# femtoUSB_r1_0_0_panelized.net
KiCad netlist of a schematic drawn in EAGLE
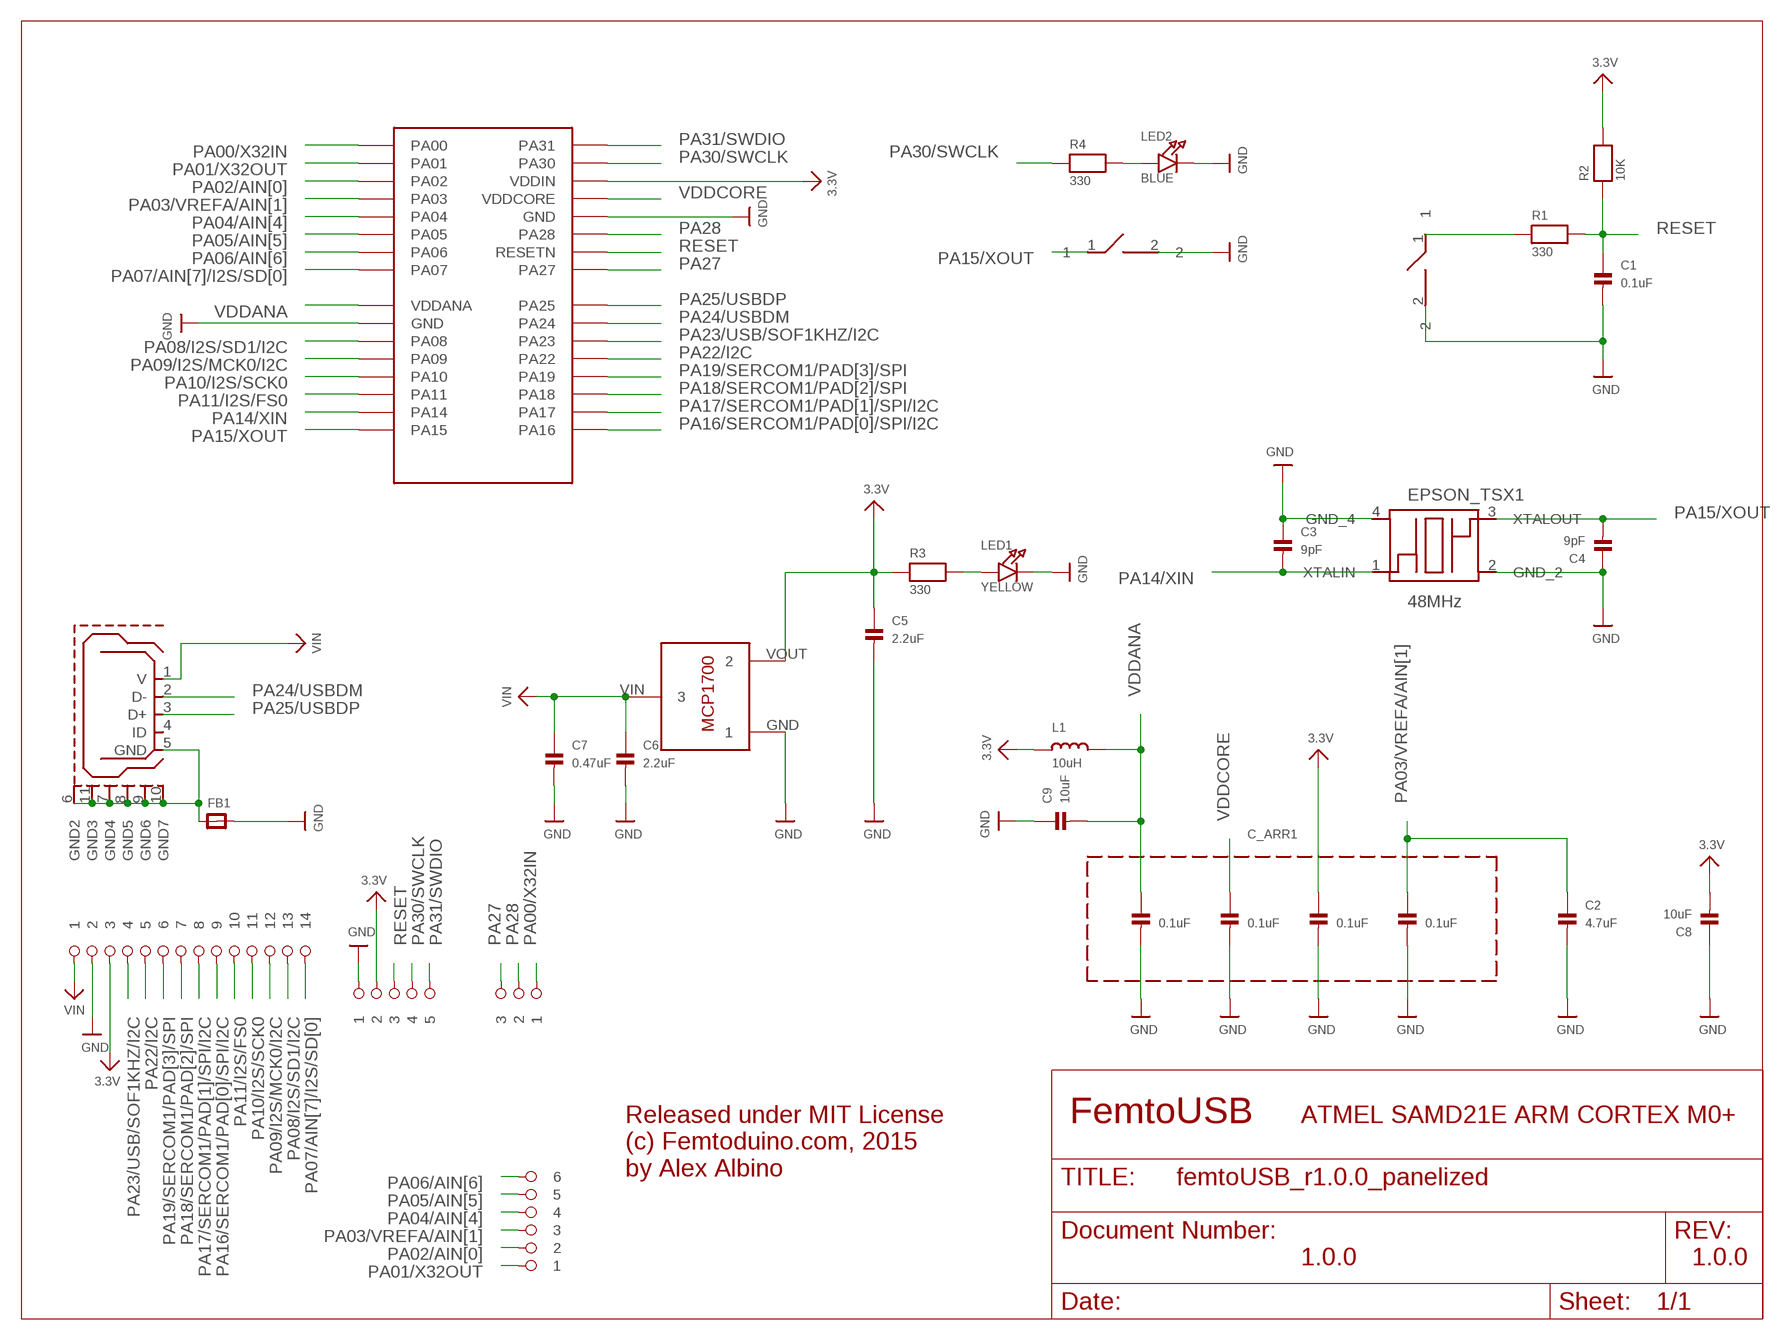
[diagram p0: schematic, sheet 1]

(export (version "E")
  (design (tool "Eeschema 10.0.6"))
  (components
    (comp (ref "BTN")
      (value "OMRON B3U-300P(M)")
      (footprint "eagle-import:SPST_SMD")
      (libsource (lib "eagle-import") (part "SPST_SMD"))
    )
    (comp (ref "C1")
      (value "0.1uF")
      (footprint "eagle-import:_0402MP")
      (libsource (lib "eagle-import") (part "CAP_CERAMIC_0402MP"))
    )
    (comp (ref "C2")
      (value "4.7uF")
      (footprint "eagle-import:_0402MP")
      (libsource (lib "eagle-import") (part "CAP_CERAMIC_0402MP"))
    )
    (comp (ref "C3")
      (value "9pF")
      (footprint "eagle-import:_0402MP")
      (libsource (lib "eagle-import") (part "CAP_CERAMIC_0402MP"))
    )
    (comp (ref "C4")
      (value "9pF")
      (footprint "eagle-import:_0402MP")
      (libsource (lib "eagle-import") (part "CAP_CERAMIC_0402MP"))
    )
    (comp (ref "C5")
      (value "2.2uF")
      (footprint "eagle-import:_0402MP")
      (libsource (lib "eagle-import") (part "CAP_CERAMIC_0402MP"))
    )
    (comp (ref "C6")
      (value "2.2uF")
      (footprint "eagle-import:_0402MP")
      (libsource (lib "eagle-import") (part "CAP_CERAMIC_0402MP"))
    )
    (comp (ref "C7")
      (value "0.47uF")
      (footprint "eagle-import:_0402MP")
      (libsource (lib "eagle-import") (part "CAP_CERAMIC_0402MP"))
    )
    (comp (ref "C8")
      (value "10uF")
      (footprint "eagle-import:_0402MP")
      (libsource (lib "eagle-import") (part "CAP_CERAMIC_0402MP"))
    )
    (comp (ref "C9")
      (value "10uF")
      (footprint "eagle-import:_0402MP")
      (libsource (lib "eagle-import") (part "CAP_CERAMIC_0402MP"))
    )
    (comp (ref "C_ARR1")
      (value "0.1uF")
      (footprint "eagle-import:CAPACITOR_ARRAY_1206_MONO_1X4")
      (libsource (lib "eagle-import") (part "KEMET_CERAMIC_CAPACITOR_ARRAY_1X4"))
    )
    (comp (ref "EPSON_TSX1")
      (value "48MHz")
      (footprint "eagle-import:TSX-3225")
      (fields (field (name "DIGIKEY_PART") "TSX-3225 32.0000MF15X-B-ND"))
      (libsource (lib "eagle-import") (part "TSX-3225"))
    )
    (comp (ref "FB1")
      (value "FERRITE_0603MP")
      (footprint "eagle-import:_0603MP")
      (libsource (lib "eagle-import") (part "FERRITE_0603MP"))
    )
    (comp (ref "IC1")
      (value "ATSAMD21E18A-MUT")
      (footprint "eagle-import:QFN32")
      (libsource (lib "eagle-import") (part "ATSAMD21E18A-MUT"))
    )
    (comp (ref "L1")
      (value "10uH")
      (footprint "eagle-import:_0603MP")
      (libsource (lib "eagle-import") (part "INDUCTOR_0603MP"))
    )
    (comp (ref "LDO_VREG")
      (value "MCP1700T-3302E/TT")
      (footprint "eagle-import:MCP1700T-3302E_TT")
      (libsource (lib "eagle-import") (part "MCP1700T-3302E/TT"))
    )
    (comp (ref "LED1")
      (value "YELLOW")
      (footprint "eagle-import:CHIPLED_0603_NOOUTLINE")
      (libsource (lib "eagle-import") (part "LED0603_NOOUTLINE"))
    )
    (comp (ref "LED2")
      (value "BLUE")
      (footprint "eagle-import:CHIPLED_0603_NOOUTLINE")
      (libsource (lib "eagle-import") (part "LED0603_NOOUTLINE"))
    )
    (comp (ref "MICRO_B_USB")
      (value "USB_MICROB")
      (footprint "eagle-import:USB_MICROB_PACKAGE")
      (libsource (lib "eagle-import") (part "USB_MICROB"))
    )
    (comp (ref "R1")
      (value "330")
      (footprint "eagle-import:_0402MP")
      (libsource (lib "eagle-import") (part "RESISTOR_0402MP"))
    )
    (comp (ref "R2")
      (value "10K")
      (footprint "eagle-import:_0402MP")
      (libsource (lib "eagle-import") (part "RESISTOR_0402MP"))
    )
    (comp (ref "R3")
      (value "330")
      (footprint "eagle-import:_0402MP")
      (libsource (lib "eagle-import") (part "RESISTOR_0402MP"))
    )
    (comp (ref "R4")
      (value "330")
      (footprint "eagle-import:_0402MP")
      (libsource (lib "eagle-import") (part "RESISTOR_0402MP"))
    )
    (comp (ref "U$6")
      (value "1X14_ROUND")
      (footprint "eagle-import:1X14_ROUND")
      (libsource (lib "eagle-import") (part "1X14_ROUND"))
    )
    (comp (ref "U$7")
      (value "1X3_ROUND")
      (footprint "eagle-import:1X3_ROUND")
      (libsource (lib "eagle-import") (part "1X3_ROUND"))
    )
    (comp (ref "U$9")
      (value "1X5_ROUND")
      (footprint "eagle-import:1X5_ROUND")
      (libsource (lib "eagle-import") (part "1X5_ROUND"))
    )
    (comp (ref "U$12")
      (value "1X6_ROUND")
      (footprint "eagle-import:1X6_ROUND")
      (libsource (lib "eagle-import") (part "1X6_ROUND"))
    )
    (comp (ref "U$38")
      (value "SPST_SMD")
      (footprint "eagle-import:SPST_SMD")
      (libsource (lib "eagle-import") (part "SPST_SMD"))
    )
  )
  (nets
    (net (code "1") (name "/PA00{slash}X32IN") (class "Default")
      (node (ref "IC1") (pin "1") (pinfunction "PA00_1") (pintype "bidirectional"))
      (node (ref "U$7") (pin "P$1") (pinfunction "1_P$1") (pintype "bidirectional"))
    )
    (net (code "2") (name "/PA01{slash}X32OUT") (class "Default")
      (node (ref "IC1") (pin "2") (pinfunction "PA01_2") (pintype "bidirectional"))
      (node (ref "U$12") (pin "P$1") (pinfunction "1_P$1") (pintype "bidirectional"))
    )
    (net (code "3") (name "/PA02{slash}AIN[0]") (class "Default")
      (node (ref "IC1") (pin "3") (pinfunction "PA02_3") (pintype "bidirectional"))
      (node (ref "U$12") (pin "P$2") (pinfunction "2_P$2") (pintype "bidirectional"))
    )
    (net (code "4") (name "/PA03{slash}VREFA{slash}AIN[1]") (class "Default")
      (node (ref "C2") (pin "1") (pinfunction "P$1_1") (pintype "passive"))
      (node (ref "C_ARR1") (pin "7") (pinfunction "P$7_7") (pintype "passive"))
      (node (ref "IC1") (pin "4") (pinfunction "PA03_4") (pintype "bidirectional"))
      (node (ref "U$12") (pin "P$3") (pinfunction "3_P$3") (pintype "bidirectional"))
    )
    (net (code "5") (name "/PA04{slash}AIN[4]") (class "Default")
      (node (ref "IC1") (pin "5") (pinfunction "PA04_5") (pintype "bidirectional"))
      (node (ref "U$12") (pin "P$4") (pinfunction "4_P$4") (pintype "bidirectional"))
    )
    (net (code "6") (name "/PA05{slash}AIN[5]") (class "Default")
      (node (ref "IC1") (pin "6") (pinfunction "PA05_6") (pintype "bidirectional"))
      (node (ref "U$12") (pin "P$5") (pinfunction "5_P$5") (pintype "bidirectional"))
    )
    (net (code "7") (name "/PA06{slash}AIN[6]") (class "Default")
      (node (ref "IC1") (pin "7") (pinfunction "PA06_7") (pintype "bidirectional"))
      (node (ref "U$12") (pin "P$6") (pinfunction "6_P$6") (pintype "bidirectional"))
    )
    (net (code "8") (name "/PA07{slash}AIN[7]{slash}I2S{slash}SD[0]") (class "Default")
      (node (ref "IC1") (pin "8") (pinfunction "PA07_8") (pintype "bidirectional"))
      (node (ref "U$6") (pin "P$14") (pinfunction "14_P$14") (pintype "bidirectional"))
    )
    (net (code "9") (name "/PA08{slash}I2S{slash}SD1{slash}I2C") (class "Default")
      (node (ref "IC1") (pin "11") (pinfunction "PA08_11") (pintype "bidirectional"))
      (node (ref "U$6") (pin "P$13") (pinfunction "13_P$13") (pintype "bidirectional"))
    )
    (net (code "10") (name "/PA09{slash}I2S{slash}MCK0{slash}I2C") (class "Default")
      (node (ref "IC1") (pin "12") (pinfunction "PA09_12") (pintype "bidirectional"))
      (node (ref "U$6") (pin "P$12") (pinfunction "12_P$12") (pintype "bidirectional"))
    )
    (net (code "11") (name "/PA10{slash}I2S{slash}SCK0") (class "Default")
      (node (ref "IC1") (pin "13") (pinfunction "PA10_13") (pintype "bidirectional"))
      (node (ref "U$6") (pin "P$11") (pinfunction "11_P$11") (pintype "bidirectional"))
    )
    (net (code "12") (name "/PA11{slash}I2S{slash}FS0") (class "Default")
      (node (ref "IC1") (pin "14") (pinfunction "PA11_14") (pintype "bidirectional"))
      (node (ref "U$6") (pin "P$10") (pinfunction "10_P$10") (pintype "bidirectional"))
    )
    (net (code "13") (name "/PA14{slash}XIN") (class "Default")
      (node (ref "C3") (pin "2") (pinfunction "P$2_2") (pintype "passive"))
      (node (ref "EPSON_TSX1") (pin "1") (pinfunction "XTALIN_1") (pintype "bidirectional"))
      (node (ref "IC1") (pin "15") (pinfunction "PA14_15") (pintype "bidirectional"))
    )
    (net (code "14") (name "/PA15{slash}XOUT") (class "Default")
      (node (ref "C4") (pin "2") (pinfunction "P$2_2") (pintype "passive"))
      (node (ref "EPSON_TSX1") (pin "3") (pinfunction "XTALOUT_3") (pintype "bidirectional"))
      (node (ref "IC1") (pin "16") (pinfunction "PA15_16") (pintype "bidirectional"))
      (node (ref "U$38") (pin "1") (pinfunction "1_1") (pintype "bidirectional"))
    )
    (net (code "15") (name "/PA16{slash}SERCOM1{slash}PAD[0]{slash}SPI{slash}I2C") (class "Default")
      (node (ref "IC1") (pin "17") (pinfunction "PA16_17") (pintype "bidirectional"))
      (node (ref "U$6") (pin "P$9") (pinfunction "9_P$9") (pintype "bidirectional"))
    )
    (net (code "16") (name "/PA17{slash}SERCOM1{slash}PAD[1]{slash}SPI{slash}I2C") (class "Default")
      (node (ref "IC1") (pin "18") (pinfunction "PA17_18") (pintype "bidirectional"))
      (node (ref "U$6") (pin "P$8") (pinfunction "8_P$8") (pintype "bidirectional"))
    )
    (net (code "17") (name "/PA18{slash}SERCOM1{slash}PAD[2]{slash}SPI") (class "Default")
      (node (ref "IC1") (pin "19") (pinfunction "PA18_19") (pintype "bidirectional"))
      (node (ref "U$6") (pin "P$7") (pinfunction "7_P$7") (pintype "bidirectional"))
    )
    (net (code "18") (name "/PA19{slash}SERCOM1{slash}PAD[3]{slash}SPI") (class "Default")
      (node (ref "IC1") (pin "20") (pinfunction "PA19_20") (pintype "bidirectional"))
      (node (ref "U$6") (pin "P$6") (pinfunction "6_P$6") (pintype "bidirectional"))
    )
    (net (code "19") (name "/PA22{slash}I2C") (class "Default")
      (node (ref "IC1") (pin "21") (pinfunction "PA22_21") (pintype "bidirectional"))
      (node (ref "U$6") (pin "P$5") (pinfunction "5_P$5") (pintype "bidirectional"))
    )
    (net (code "20") (name "/PA23{slash}USB{slash}SOF1KHZ{slash}I2C") (class "Default")
      (node (ref "IC1") (pin "22") (pinfunction "PA23_22") (pintype "bidirectional"))
      (node (ref "U$6") (pin "P$4") (pinfunction "4_P$4") (pintype "bidirectional"))
    )
    (net (code "21") (name "/PA24{slash}USBDM") (class "Default")
      (node (ref "IC1") (pin "23") (pinfunction "PA24_23") (pintype "bidirectional"))
      (node (ref "MICRO_B_USB") (pin "2") (pinfunction "D-_2") (pintype "bidirectional"))
    )
    (net (code "22") (name "/PA25{slash}USBDP") (class "Default")
      (node (ref "IC1") (pin "24") (pinfunction "PA25_24") (pintype "bidirectional"))
      (node (ref "MICRO_B_USB") (pin "3") (pinfunction "D+_3") (pintype "bidirectional"))
    )
    (net (code "23") (name "/PA27") (class "Default")
      (node (ref "IC1") (pin "25") (pinfunction "PA27_25") (pintype "bidirectional"))
      (node (ref "U$7") (pin "P$3") (pinfunction "3_P$3") (pintype "bidirectional"))
    )
    (net (code "24") (name "/PA28") (class "Default")
      (node (ref "IC1") (pin "27") (pinfunction "PA28_27") (pintype "bidirectional"))
      (node (ref "U$7") (pin "P$2") (pinfunction "2_P$2") (pintype "bidirectional"))
    )
    (net (code "25") (name "/PA30{slash}SWCLK") (class "Default")
      (node (ref "IC1") (pin "31") (pinfunction "PA30_31") (pintype "bidirectional"))
      (node (ref "R4") (pin "1") (pinfunction "1_1") (pintype "passive"))
      (node (ref "U$9") (pin "P$4") (pinfunction "4_P$4") (pintype "bidirectional"))
    )
    (net (code "26") (name "/PA31{slash}SWDIO") (class "Default")
      (node (ref "IC1") (pin "32") (pinfunction "PA31_32") (pintype "bidirectional"))
      (node (ref "U$9") (pin "P$5") (pinfunction "5_P$5") (pintype "bidirectional"))
    )
    (net (code "27") (name "/RESET") (class "Default")
      (node (ref "C1") (pin "1") (pinfunction "P$1_1") (pintype "passive"))
      (node (ref "IC1") (pin "26") (pinfunction "RESETN_26") (pintype "bidirectional"))
      (node (ref "R1") (pin "2") (pinfunction "2_2") (pintype "passive"))
      (node (ref "R2") (pin "1") (pinfunction "1_1") (pintype "passive"))
      (node (ref "U$9") (pin "P$3") (pinfunction "3_P$3") (pintype "bidirectional"))
    )
    (net (code "28") (name "/VDDANA") (class "Default")
      (node (ref "C9") (pin "2") (pinfunction "P$2_2") (pintype "passive"))
      (node (ref "C_ARR1") (pin "1") (pinfunction "P$1_1") (pintype "passive"))
      (node (ref "IC1") (pin "9") (pinfunction "VDDANA_9") (pintype "bidirectional"))
      (node (ref "L1") (pin "2") (pinfunction "2_2") (pintype "passive"))
    )
    (net (code "29") (name "/VDDCORE") (class "Default")
      (node (ref "C_ARR1") (pin "3") (pinfunction "P$3_3") (pintype "passive"))
      (node (ref "IC1") (pin "29") (pinfunction "VDDCORE_29") (pintype "bidirectional"))
    )
    (net (code "30") (name "3.3V") (class "Default")
      (node (ref "C5") (pin "1") (pinfunction "P$1_1") (pintype "passive"))
      (node (ref "C8") (pin "2") (pinfunction "P$2_2") (pintype "passive"))
      (node (ref "C_ARR1") (pin "5") (pinfunction "P$5_5") (pintype "passive"))
      (node (ref "IC1") (pin "30") (pinfunction "VDDIN_30") (pintype "bidirectional"))
      (node (ref "L1") (pin "1") (pinfunction "1_1") (pintype "passive"))
      (node (ref "LDO_VREG") (pin "VOUT") (pinfunction "2_VOUT") (pintype "bidirectional"))
      (node (ref "R2") (pin "2") (pinfunction "2_2") (pintype "passive"))
      (node (ref "R3") (pin "1") (pinfunction "1_1") (pintype "passive"))
      (node (ref "U$6") (pin "P$3") (pinfunction "3_P$3") (pintype "bidirectional"))
      (node (ref "U$9") (pin "P$2") (pinfunction "2_P$2") (pintype "bidirectional"))
    )
    (net (code "31") (name "GND") (class "Default")
      (node (ref "BTN") (pin "2") (pinfunction "2_2") (pintype "bidirectional"))
      (node (ref "C1") (pin "2") (pinfunction "P$2_2") (pintype "passive"))
      (node (ref "C2") (pin "2") (pinfunction "P$2_2") (pintype "passive"))
      (node (ref "C3") (pin "1") (pinfunction "P$1_1") (pintype "passive"))
      (node (ref "C4") (pin "1") (pinfunction "P$1_1") (pintype "passive"))
      (node (ref "C5") (pin "2") (pinfunction "P$2_2") (pintype "passive"))
      (node (ref "C6") (pin "2") (pinfunction "P$2_2") (pintype "passive"))
      (node (ref "C7") (pin "2") (pinfunction "P$2_2") (pintype "passive"))
      (node (ref "C8") (pin "1") (pinfunction "P$1_1") (pintype "passive"))
      (node (ref "C9") (pin "1") (pinfunction "P$1_1") (pintype "passive"))
      (node (ref "C_ARR1") (pin "2") (pinfunction "P$2_2") (pintype "passive"))
      (node (ref "C_ARR1") (pin "4") (pinfunction "P$4_4") (pintype "passive"))
      (node (ref "C_ARR1") (pin "6") (pinfunction "P$6_6") (pintype "passive"))
      (node (ref "C_ARR1") (pin "8") (pinfunction "P$8_8") (pintype "passive"))
      (node (ref "EPSON_TSX1") (pin "2") (pinfunction "GND_2_2") (pintype "bidirectional"))
      (node (ref "EPSON_TSX1") (pin "4") (pinfunction "GND_4_4") (pintype "bidirectional"))
      (node (ref "FB1") (pin "2") (pinfunction "P$2_2") (pintype "passive"))
      (node (ref "IC1") (pin "10") (pinfunction "GND_10") (pintype "bidirectional"))
      (node (ref "IC1") (pin "28") (pinfunction "GND_28") (pintype "bidirectional"))
      (node (ref "LDO_VREG") (pin "GND") (pinfunction "1_GND") (pintype "bidirectional"))
      (node (ref "LED1") (pin "C") (pinfunction "C_C") (pintype "passive"))
      (node (ref "LED2") (pin "C") (pinfunction "C_C") (pintype "passive"))
      (node (ref "U$38") (pin "2") (pinfunction "2_2") (pintype "bidirectional"))
      (node (ref "U$6") (pin "P$2") (pinfunction "2_P$2") (pintype "bidirectional"))
      (node (ref "U$9") (pin "P$1") (pinfunction "1_P$1") (pintype "bidirectional"))
    )
    (net (code "32") (name "Net-(BTN-Pad1)") (class "Default")
      (node (ref "BTN") (pin "1") (pinfunction "1_1") (pintype "bidirectional"))
      (node (ref "R1") (pin "1") (pinfunction "1_1") (pintype "passive"))
    )
    (net (code "33") (name "Net-(FB1-P$1)") (class "Default")
      (node (ref "FB1") (pin "1") (pinfunction "P$1_1") (pintype "passive"))
      (node (ref "MICRO_B_USB") (pin "10") (pinfunction "GND7_10") (pintype "bidirectional"))
      (node (ref "MICRO_B_USB") (pin "11") (pinfunction "GND3_11") (pintype "bidirectional"))
      (node (ref "MICRO_B_USB") (pin "5") (pinfunction "GND_5") (pintype "bidirectional"))
      (node (ref "MICRO_B_USB") (pin "6") (pinfunction "GND2_6") (pintype "bidirectional"))
      (node (ref "MICRO_B_USB") (pin "7") (pinfunction "GND4_7") (pintype "bidirectional"))
      (node (ref "MICRO_B_USB") (pin "8") (pinfunction "GND5_8") (pintype "bidirectional"))
      (node (ref "MICRO_B_USB") (pin "9") (pinfunction "GND6_9") (pintype "bidirectional"))
    )
    (net (code "34") (name "Net-(LED1-PadA)") (class "Default")
      (node (ref "LED1") (pin "A") (pinfunction "A_A") (pintype "passive"))
      (node (ref "R3") (pin "2") (pinfunction "2_2") (pintype "passive"))
    )
    (net (code "35") (name "Net-(LED2-PadA)") (class "Default")
      (node (ref "LED2") (pin "A") (pinfunction "A_A") (pintype "passive"))
      (node (ref "R4") (pin "2") (pinfunction "2_2") (pintype "passive"))
    )
    (net (code "36") (name "VIN") (class "Default")
      (node (ref "C6") (pin "1") (pinfunction "P$1_1") (pintype "passive"))
      (node (ref "C7") (pin "1") (pinfunction "P$1_1") (pintype "passive"))
      (node (ref "LDO_VREG") (pin "VIN") (pinfunction "3_VIN") (pintype "bidirectional"))
      (node (ref "MICRO_B_USB") (pin "1") (pinfunction "V_1") (pintype "bidirectional"))
      (node (ref "U$6") (pin "P$1") (pinfunction "1_P$1") (pintype "bidirectional"))
    )
    (net (code "37") (name "unconnected-(MICRO_B_USB-ID-Pad4)") (class "Default")
      (node (ref "MICRO_B_USB") (pin "4") (pinfunction "ID_4") (pintype "bidirectional"))
    )
  )
)
